# SparkFun_ENS160_BME280_Breakout.net
KiCad netlist of a schematic drawn in EAGLE
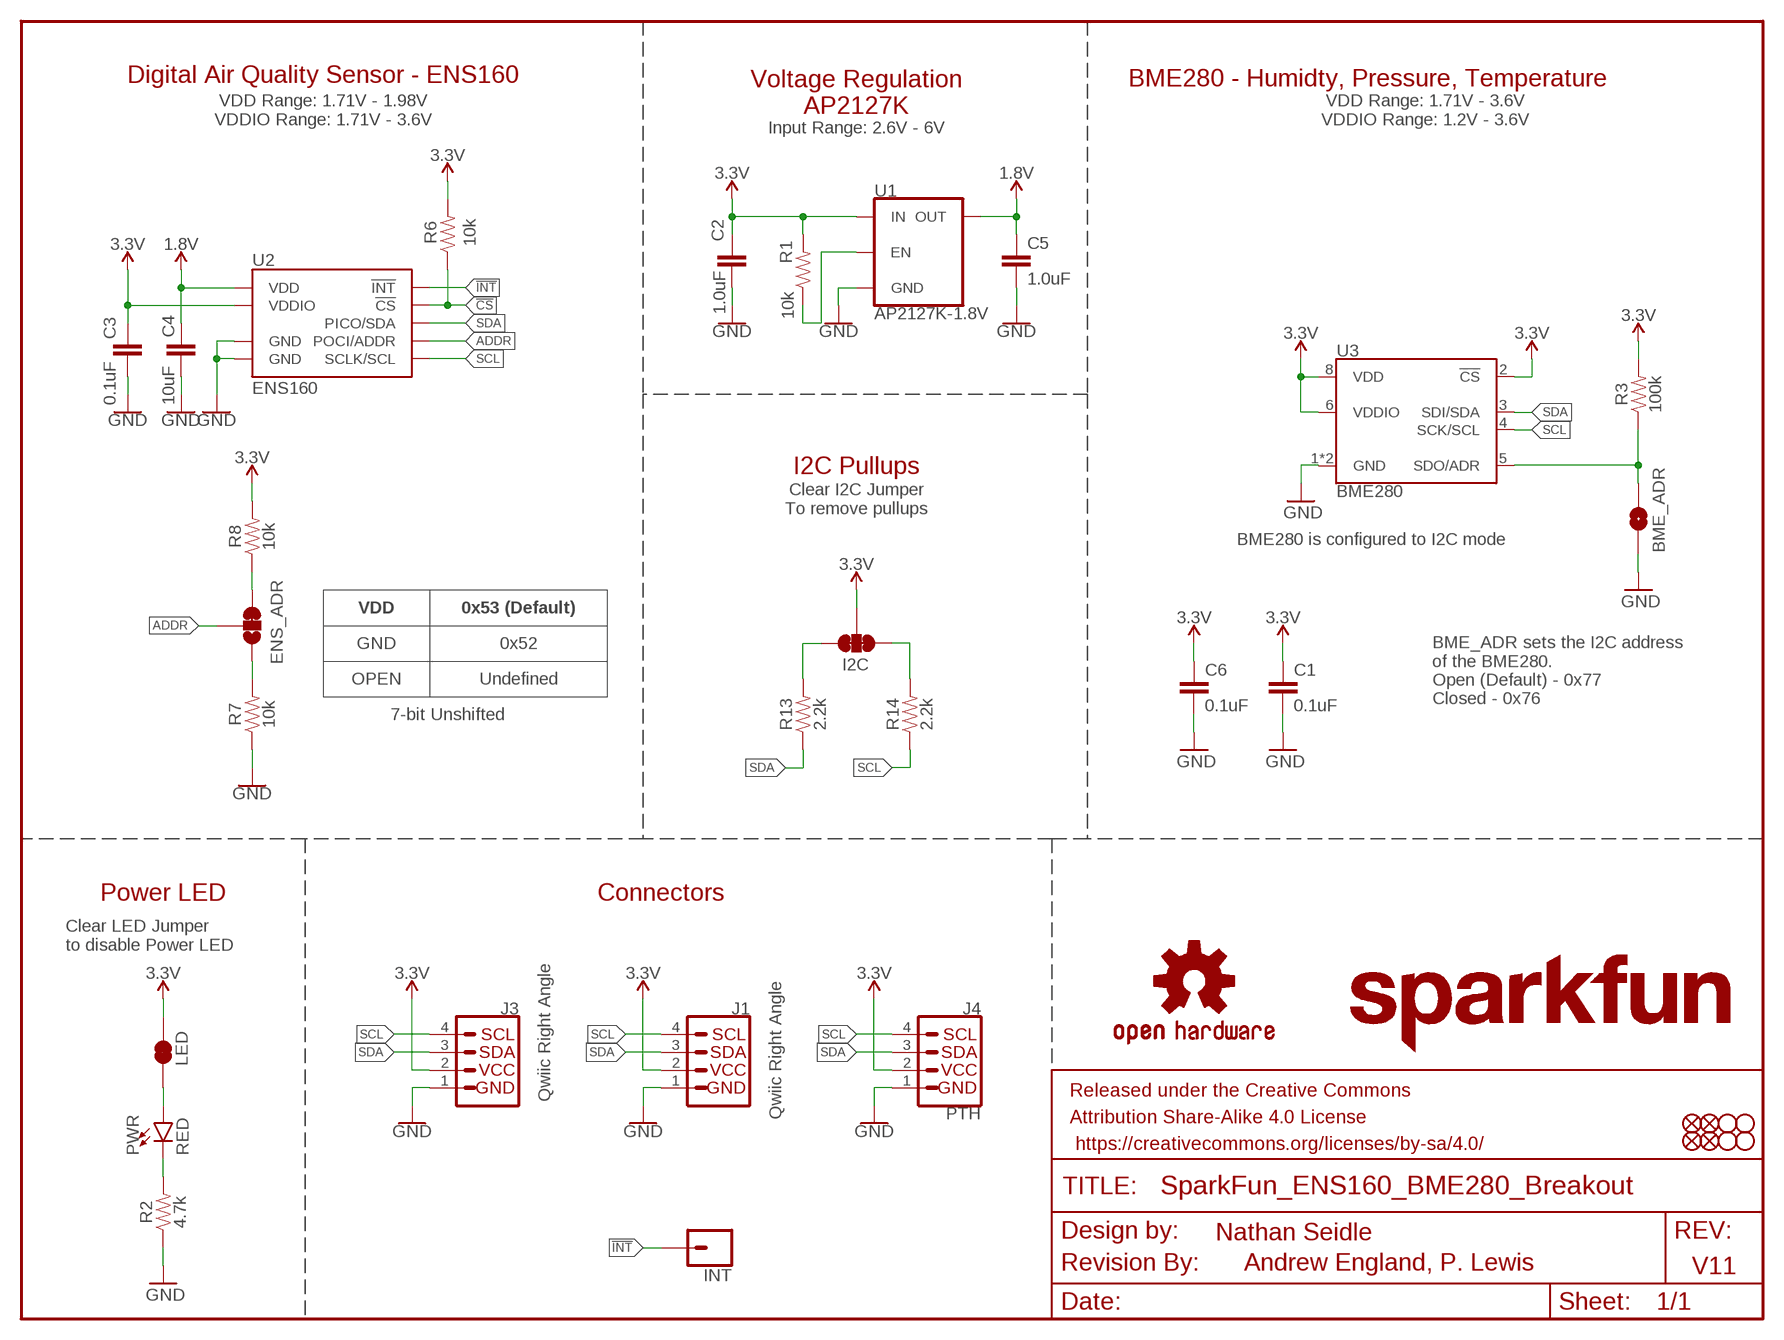
[diagram p0: schematic, sheet 1]

(export (version "E")
  (design (tool "Eeschema 10.0.6"))
  (components
    (comp (ref "BME_ADR")
      (value "JUMPER-SMT_2_NO_SILK")
      (footprint "eagle-import:SMT-JUMPER_2_NO_SILK")
      (libsource (lib "eagle-import") (part "JUMPER-SMT_2_NO_SILK"))
    )
    (comp (ref "C1")
      (value "0.1uF")
      (footprint "eagle-import:0402-TIGHT")
      (libsource (lib "eagle-import") (part "0.1UF-0402T-16V-10%"))
    )
    (comp (ref "C2")
      (value "1.0uF")
      (footprint "eagle-import:0402-TIGHT")
      (libsource (lib "eagle-import") (part "1.0UF-0402T-16V-10%"))
    )
    (comp (ref "C3")
      (value "0.1uF")
      (footprint "eagle-import:0402-TIGHT")
      (libsource (lib "eagle-import") (part "0.1UF-0402T-16V-10%"))
    )
    (comp (ref "C4")
      (value "10uF")
      (footprint "eagle-import:0402-TIGHT")
      (libsource (lib "eagle-import") (part "10UF-0402T-6.3V-20%"))
    )
    (comp (ref "C5")
      (value "1.0uF")
      (footprint "eagle-import:0402-TIGHT")
      (libsource (lib "eagle-import") (part "1.0UF-0402T-16V-10%"))
    )
    (comp (ref "C6")
      (value "0.1uF")
      (footprint "eagle-import:0402-TIGHT")
      (libsource (lib "eagle-import") (part "0.1UF-0402T-16V-10%"))
    )
    (comp (ref "ENS_ADR")
      (value "JUMPER-SMT_3_1-NC_TRACE_SILK")
      (footprint "eagle-import:SMT-JUMPER_3_1-NC_TRACE_SILK")
      (libsource (lib "eagle-import") (part "JUMPER-SMT_3_1-NC_TRACE_SILK"))
    )
    (comp (ref "FD1")
      (value "FIDUCIAL1X2")
      (footprint "eagle-import:FIDUCIAL-1X2")
      (libsource (lib "eagle-import") (part "FIDUCIAL1X2"))
    )
    (comp (ref "FD2")
      (value "FIDUCIAL1X2")
      (footprint "eagle-import:FIDUCIAL-1X2")
      (libsource (lib "eagle-import") (part "FIDUCIAL1X2"))
    )
    (comp (ref "FD3")
      (value "FIDUCIAL1X2")
      (footprint "eagle-import:FIDUCIAL-1X2")
      (libsource (lib "eagle-import") (part "FIDUCIAL1X2"))
    )
    (comp (ref "FD4")
      (value "FIDUCIAL1X2")
      (footprint "eagle-import:FIDUCIAL-1X2")
      (libsource (lib "eagle-import") (part "FIDUCIAL1X2"))
    )
    (comp (ref "FRAME1")
      (value "FRAME-LETTER")
      (footprint "eagle-import:CREATIVE_COMMONS")
      (libsource (lib "eagle-import") (part "FRAME-LETTER"))
    )
    (comp (ref "H1")
      (value "STAND-OFF")
      (footprint "eagle-import:STAND-OFF")
      (libsource (lib "eagle-import") (part "STAND-OFF"))
    )
    (comp (ref "H2")
      (value "STAND-OFF")
      (footprint "eagle-import:STAND-OFF")
      (libsource (lib "eagle-import") (part "STAND-OFF"))
    )
    (comp (ref "H3")
      (value "STAND-OFF")
      (footprint "eagle-import:STAND-OFF")
      (libsource (lib "eagle-import") (part "STAND-OFF"))
    )
    (comp (ref "H4")
      (value "STAND-OFF")
      (footprint "eagle-import:STAND-OFF")
      (libsource (lib "eagle-import") (part "STAND-OFF"))
    )
    (comp (ref "I2C")
      (value "JUMPER-SMT_3_2-NC_TRACE_SILK")
      (footprint "eagle-import:SMT-JUMPER_3_2-NC_TRACE_SILK")
      (libsource (lib "eagle-import") (part "JUMPER-SMT_3_2-NC_TRACE_SILK"))
    )
    (comp (ref "INT")
      (value "CONN_01PTH_NO_SILK_STAND")
      (footprint "eagle-import:1X01_NO_SILK_STAND")
      (libsource (lib "eagle-import") (part "CONN_01PTH_NO_SILK_STAND"))
    )
    (comp (ref "J1")
      (value "Qwiic Right Angle")
      (footprint "eagle-import:JST04_1MM_RA")
      (libsource (lib "eagle-import") (part "I2C_STANDARDQWIIC"))
    )
    (comp (ref "J3")
      (value "Qwiic Right Angle")
      (footprint "eagle-import:JST04_1MM_RA")
      (libsource (lib "eagle-import") (part "I2C_STANDARDQWIIC"))
    )
    (comp (ref "J4")
      (value "PTH")
      (footprint "eagle-import:1X04_NO_SILK")
      (libsource (lib "eagle-import") (part "I2C_STANDARD_NO_SILK"))
    )
    (comp (ref "LED")
      (value "JUMPER-SMT_2_NC_TRACE_SILK")
      (footprint "eagle-import:SMT-JUMPER_2_NC_TRACE_SILK")
      (libsource (lib "eagle-import") (part "JUMPER-SMT_2_NC_TRACE_SILK"))
    )
    (comp (ref "LOGO1")
      (value "SFE_LOGO_NAME.1_INCH")
      (footprint "eagle-import:SFE_LOGO_NAME_.1")
      (libsource (lib "eagle-import") (part "SFE_LOGO_NAME.1_INCH"))
    )
    (comp (ref "LOGO2")
      (value "REVISION")
      (footprint "eagle-import:REVISION")
      (libsource (lib "eagle-import") (part "REVISION"))
    )
    (comp (ref "LOGO4")
      (value "OSHW-LOGOS")
      (footprint "eagle-import:OSHW-LOGO-S")
      (libsource (lib "eagle-import") (part "OSHW-LOGOS"))
    )
    (comp (ref "PWR")
      (value "RED")
      (footprint "eagle-import:LED-0603")
      (libsource (lib "eagle-import") (part "LED-RED_0603-KB"))
    )
    (comp (ref "R1")
      (value "10k")
      (footprint "eagle-import:0402-TIGHT")
      (libsource (lib "eagle-import") (part "10KOHM-0402T-1/16W-1%"))
    )
    (comp (ref "R2")
      (value "4.7k")
      (footprint "eagle-import:0402-TIGHT")
      (libsource (lib "eagle-import") (part "4.7KOHM-0402T-1/16W-1%"))
    )
    (comp (ref "R3")
      (value "100k")
      (footprint "eagle-import:0402-TIGHT")
      (libsource (lib "eagle-import") (part "100KOHM-0402T-1/16W-1%"))
    )
    (comp (ref "R6")
      (value "10k")
      (footprint "eagle-import:0402-TIGHT")
      (libsource (lib "eagle-import") (part "10KOHM-0402T-1/16W-1%"))
    )
    (comp (ref "R7")
      (value "10k")
      (footprint "eagle-import:0402-TIGHT")
      (libsource (lib "eagle-import") (part "10KOHM-0402T-1/16W-1%"))
    )
    (comp (ref "R8")
      (value "10k")
      (footprint "eagle-import:0402-TIGHT")
      (libsource (lib "eagle-import") (part "10KOHM-0402T-1/16W-1%"))
    )
    (comp (ref "R13")
      (value "2.2k")
      (footprint "eagle-import:0402-TIGHT")
      (libsource (lib "eagle-import") (part "2.2KOHM-0402T-1/16W-1%"))
    )
    (comp (ref "R14")
      (value "2.2k")
      (footprint "eagle-import:0402-TIGHT")
      (libsource (lib "eagle-import") (part "2.2KOHM-0402T-1/16W-1%"))
    )
    (comp (ref "U1")
      (value "AP2127K-1.8V")
      (footprint "eagle-import:SOT23-5")
      (libsource (lib "eagle-import") (part "V_REG_AP2127K-1.8V"))
    )
    (comp (ref "U2")
      (value "ENS160")
      (footprint "eagle-import:LGA-9")
      (libsource (lib "eagle-import") (part "ENS-160"))
    )
    (comp (ref "U3")
      (value "BME280")
      (footprint "eagle-import:LGA-8-2.5X2.5")
      (libsource (lib "eagle-import") (part "BME280"))
    )
  )
  (nets
    (net (code "1") (name "/~{CS}") (class "Default")
      (node (ref "R6") (pin "1") (pinfunction "1_1") (pintype "passive"))
      (node (ref "U2") (pin "P7") (pinfunction "~{CS}_P7") (pintype "bidirectional"))
    )
    (net (code "2") (name "/~{INT}") (class "Default")
      (node (ref "INT") (pin "1") (pinfunction "1_1") (pintype "passive"))
      (node (ref "U2") (pin "P6") (pinfunction "~{INT}_P6") (pintype "bidirectional"))
    )
    (net (code "3") (name "1.8V") (class "Default")
      (node (ref "C4") (pin "1") (pinfunction "1_1") (pintype "passive"))
      (node (ref "C5") (pin "1") (pinfunction "1_1") (pintype "passive"))
      (node (ref "U1") (pin "5") (pinfunction "OUT_5") (pintype "passive"))
      (node (ref "U2") (pin "P4") (pinfunction "VDD_P4") (pintype "power_in"))
    )
    (net (code "4") (name "3.3V") (class "Default")
      (node (ref "C1") (pin "1") (pinfunction "1_1") (pintype "passive"))
      (node (ref "C2") (pin "1") (pinfunction "1_1") (pintype "passive"))
      (node (ref "C3") (pin "1") (pinfunction "1_1") (pintype "passive"))
      (node (ref "C6") (pin "1") (pinfunction "1_1") (pintype "passive"))
      (node (ref "I2C") (pin "2") (pinfunction "2_2") (pintype "passive"))
      (node (ref "J1") (pin "2") (pinfunction "2_2") (pintype "power_in"))
      (node (ref "J3") (pin "2") (pinfunction "2_2") (pintype "power_in"))
      (node (ref "J4") (pin "2") (pinfunction "2_2") (pintype "power_in"))
      (node (ref "LED") (pin "1") (pinfunction "1_1") (pintype "passive"))
      (node (ref "R1") (pin "2") (pinfunction "2_2") (pintype "passive"))
      (node (ref "R3") (pin "2") (pinfunction "2_2") (pintype "passive"))
      (node (ref "R6") (pin "2") (pinfunction "2_2") (pintype "passive"))
      (node (ref "R8") (pin "2") (pinfunction "2_2") (pintype "passive"))
      (node (ref "U1") (pin "1") (pinfunction "IN_1") (pintype "input"))
      (node (ref "U2") (pin "P5") (pinfunction "VDDIO_P5") (pintype "power_in"))
      (node (ref "U3") (pin "2") (pinfunction "~{CS}_2") (pintype "bidirectional"))
      (node (ref "U3") (pin "6") (pinfunction "VDDIO_6") (pintype "bidirectional"))
      (node (ref "U3") (pin "8") (pinfunction "VDD_8") (pintype "bidirectional"))
    )
    (net (code "5") (name "ADDR") (class "Default")
      (node (ref "ENS_ADR") (pin "2") (pinfunction "2_2") (pintype "passive"))
      (node (ref "U2") (pin "P3") (pinfunction "POCI/ADDR_P3") (pintype "bidirectional"))
    )
    (net (code "6") (name "GND") (class "Default")
      (node (ref "BME_ADR") (pin "1") (pinfunction "1_1") (pintype "passive"))
      (node (ref "C1") (pin "2") (pinfunction "2_2") (pintype "passive"))
      (node (ref "C2") (pin "2") (pinfunction "2_2") (pintype "passive"))
      (node (ref "C3") (pin "2") (pinfunction "2_2") (pintype "passive"))
      (node (ref "C4") (pin "2") (pinfunction "2_2") (pintype "passive"))
      (node (ref "C5") (pin "2") (pinfunction "2_2") (pintype "passive"))
      (node (ref "C6") (pin "2") (pinfunction "2_2") (pintype "passive"))
      (node (ref "J1") (pin "1") (pinfunction "1_1") (pintype "power_in"))
      (node (ref "J3") (pin "1") (pinfunction "1_1") (pintype "power_in"))
      (node (ref "J4") (pin "1") (pinfunction "1_1") (pintype "power_in"))
      (node (ref "R2") (pin "1") (pinfunction "1_1") (pintype "passive"))
      (node (ref "R7") (pin "1") (pinfunction "1_1") (pintype "passive"))
      (node (ref "U1") (pin "2") (pinfunction "GND_2") (pintype "input"))
      (node (ref "U2") (pin "P8") (pinfunction "GND_P8") (pintype "power_in"))
      (node (ref "U2") (pin "P9") (pinfunction "GND_P9") (pintype "power_in"))
      (node (ref "U3") (pin "1") (pinfunction "GND_1") (pintype "bidirectional"))
      (node (ref "U3") (pin "7") (pinfunction "GND_7") (pintype "bidirectional"))
    )
    (net (code "7") (name "Net-(ENS_ADR-Pad1)") (class "Default")
      (node (ref "ENS_ADR") (pin "1") (pinfunction "1_1") (pintype "passive"))
      (node (ref "R7") (pin "2") (pinfunction "2_2") (pintype "passive"))
    )
    (net (code "8") (name "Net-(ENS_ADR-Pad3)") (class "Default")
      (node (ref "ENS_ADR") (pin "3") (pinfunction "3_3") (pintype "passive"))
      (node (ref "R8") (pin "1") (pinfunction "1_1") (pintype "passive"))
    )
    (net (code "9") (name "Net-(I2C-Pad1)") (class "Default")
      (node (ref "I2C") (pin "1") (pinfunction "1_1") (pintype "passive"))
      (node (ref "R14") (pin "2") (pinfunction "2_2") (pintype "passive"))
    )
    (net (code "10") (name "Net-(I2C-Pad3)") (class "Default")
      (node (ref "I2C") (pin "3") (pinfunction "3_3") (pintype "passive"))
      (node (ref "R13") (pin "2") (pinfunction "2_2") (pintype "passive"))
    )
    (net (code "11") (name "Net-(LED-Pad2)") (class "Default")
      (node (ref "LED") (pin "2") (pinfunction "2_2") (pintype "passive"))
      (node (ref "PWR") (pin "A") (pinfunction "A_A") (pintype "passive"))
    )
    (net (code "12") (name "Net-(PWR-PadC)") (class "Default")
      (node (ref "PWR") (pin "C") (pinfunction "C_C") (pintype "passive"))
      (node (ref "R2") (pin "2") (pinfunction "2_2") (pintype "passive"))
    )
    (net (code "13") (name "Net-(U1-EN)") (class "Default")
      (node (ref "R1") (pin "1") (pinfunction "1_1") (pintype "passive"))
      (node (ref "U1") (pin "3") (pinfunction "EN_3") (pintype "input"))
    )
    (net (code "14") (name "Net-(U3-SDO{slash}ADR)") (class "Default")
      (node (ref "BME_ADR") (pin "2") (pinfunction "2_2") (pintype "passive"))
      (node (ref "R3") (pin "1") (pinfunction "1_1") (pintype "passive"))
      (node (ref "U3") (pin "5") (pinfunction "SDO/ADR_5") (pintype "bidirectional"))
    )
    (net (code "15") (name "SCL") (class "Default")
      (node (ref "J1") (pin "4") (pinfunction "4_4") (pintype "passive"))
      (node (ref "J3") (pin "4") (pinfunction "4_4") (pintype "passive"))
      (node (ref "J4") (pin "4") (pinfunction "4_4") (pintype "passive"))
      (node (ref "R14") (pin "1") (pinfunction "1_1") (pintype "passive"))
      (node (ref "U2") (pin "P2") (pinfunction "SCLK/SCL_P2") (pintype "bidirectional"))
      (node (ref "U3") (pin "4") (pinfunction "SCK/SCL_4") (pintype "bidirectional"))
    )
    (net (code "16") (name "SDA") (class "Default")
      (node (ref "J1") (pin "3") (pinfunction "3_3") (pintype "passive"))
      (node (ref "J3") (pin "3") (pinfunction "3_3") (pintype "passive"))
      (node (ref "J4") (pin "3") (pinfunction "3_3") (pintype "passive"))
      (node (ref "R13") (pin "1") (pinfunction "1_1") (pintype "passive"))
      (node (ref "U2") (pin "P1") (pinfunction "PICO/SDA_P1") (pintype "bidirectional"))
      (node (ref "U3") (pin "3") (pinfunction "SDI/SDA_3") (pintype "bidirectional"))
    )
  )
)
